# 02_stm32_power.net
KiCad netlist of a schematic drawn in Altium Designer
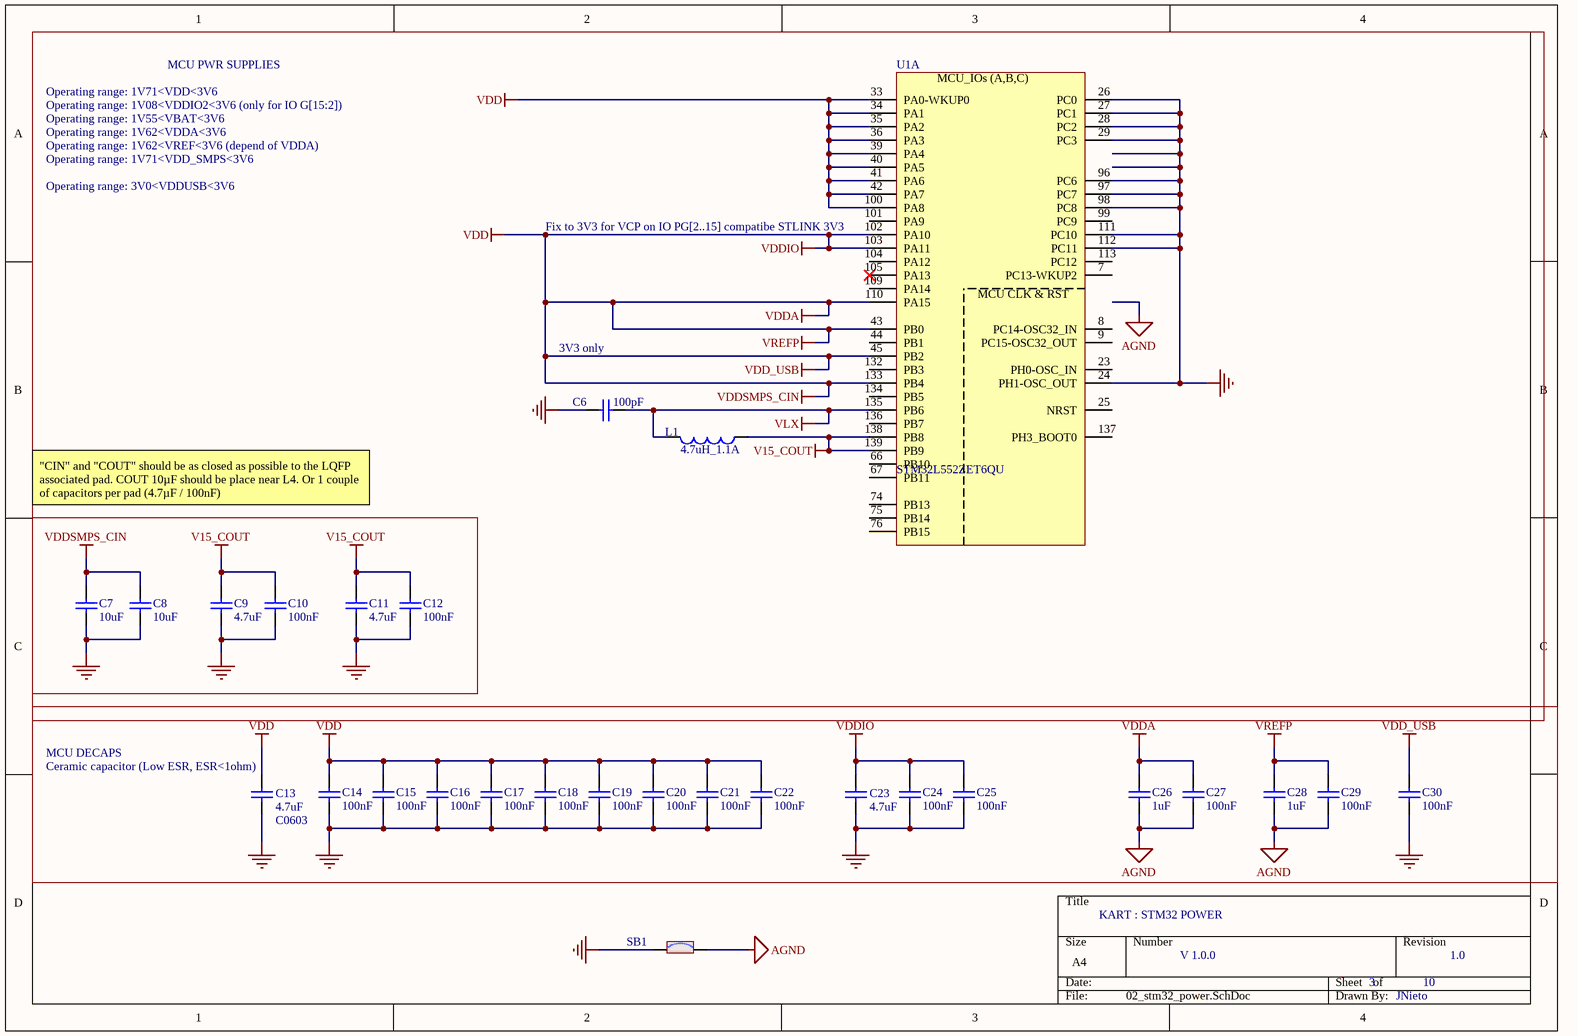
[diagram p0: 02_stm32_power.SchDoc]

(export (version "E")
  (design (tool "Eeschema 10.0.6"))
  (components
    (comp (ref "C6")
      (value "100pF")
      (footprint "C0603")
      (description "Capacitor, MLCC, 100pF, 50V, NPO, 5%, 0402, T=0,5mm")
      (fields
        (field (name "INTERNAL_PART_NUMBER") "MCD-00205")
        (field (name "MANUFACTURER_PART_NUMBER") "CC0402JRNPO9BN101")
        (field (name "PROVIDED_BY") "Subcon")
      )
      (libsource (lib "MCD_PARTS_database") (part "Capacitor"))
    )
    (comp (ref "C7")
      (value "10uF")
      (footprint "C0603")
      (description "Capacitor, MLCC, 10uF, 4V, X5R, 20%, 0402, T=0,5mm")
      (fields
        (field (name "INTERNAL_PART_NUMBER") "MCD-01355")
        (field (name "MANUFACTURER_PART_NUMBER") "GRM155R60G106ME44")
        (field (name "PROVIDED_BY") "Subcon")
      )
      (libsource (lib "MCD_PARTS_database") (part "Capacitor"))
    )
    (comp (ref "C8")
      (value "10uF")
      (footprint "C0603")
      (description "Capacitor, MLCC, 10uF, 4V, X5R, 20%, 0402, T=0,5mm")
      (fields
        (field (name "INTERNAL_PART_NUMBER") "MCD-01355")
        (field (name "MANUFACTURER_PART_NUMBER") "GRM155R60G106ME44")
        (field (name "PROVIDED_BY") "Subcon")
      )
      (libsource (lib "MCD_PARTS_database") (part "Capacitor"))
    )
    (comp (ref "C9")
      (value "4.7uF")
      (footprint "C0603")
      (description "Capacitor, MLCC, 4.7uF, 6V3, X5R, 20%, 0402, T=0,5mm")
      (fields
        (field (name "INTERNAL_PART_NUMBER") "MCD-01356")
        (field (name "MANUFACTURER_PART_NUMBER") "GRM155R60J475ME47")
        (field (name "PROVIDED_BY") "Subcon")
      )
      (libsource (lib "MCD_PARTS_database") (part "Capacitor"))
    )
    (comp (ref "C10")
      (value "100nF")
      (footprint "C0603")
      (description "Capacitor, MLCC, 100nF, 16V, X5R, 10%, 0603, T=0,8mm")
      (fields
        (field (name "INTERNAL_PART_NUMBER") "MCD-00010")
        (field (name "MANUFACTURER_PART_NUMBER") "CC0603KRX5R7BB105")
        (field (name "PROVIDED_BY") "SUBCO")
      )
      (libsource (lib "MCD_PARTS_database") (part "Capacitor"))
    )
    (comp (ref "C11")
      (value "4.7uF")
      (footprint "C0603")
      (description "Capacitor, MLCC, 4.7uF, 6V3, X5R, 20%, 0402, T=0,5mm")
      (fields
        (field (name "INTERNAL_PART_NUMBER") "MCD-01356")
        (field (name "MANUFACTURER_PART_NUMBER") "GRM155R60J475ME47")
        (field (name "PROVIDED_BY") "Subcon")
      )
      (libsource (lib "MCD_PARTS_database") (part "Capacitor"))
    )
    (comp (ref "C12")
      (value "100nF")
      (footprint "C0603")
      (description "Capacitor, MLCC, 100nF, 16V, X5R, 10%, 0603, T=0,8mm")
      (fields
        (field (name "INTERNAL_PART_NUMBER") "MCD-00010")
        (field (name "MANUFACTURER_PART_NUMBER") "CC0603KRX5R7BB105")
        (field (name "PROVIDED_BY") "SUBCO")
      )
      (libsource (lib "MCD_PARTS_database") (part "Capacitor"))
    )
    (comp (ref "C13")
      (value "4.7uF")
      (footprint "C0603")
      (description "Capacitor, MLCC, 4.7µF, 10V, X5R, 20%, 0603, T=0,8mm")
      (fields
        (field (name "INTERNAL_PART_NUMBER") "MCD-01121")
        (field (name "MANUFACTURER_PART_NUMBER") "GRM188R61A475ME15")
        (field (name "PACKAGE") "C0603")
        (field (name "PROVIDED_BY") "Subcon")
      )
      (libsource (lib "MCD_PARTS_database") (part "Capacitor"))
    )
    (comp (ref "C14")
      (value "100nF")
      (footprint "C0603")
      (description "Capacitor, MLCC, 100nF, 16V, X5R, 10%, 0603, T=0,8mm")
      (fields
        (field (name "INTERNAL_PART_NUMBER") "MCD-00010")
        (field (name "MANUFACTURER_PART_NUMBER") "CC0603KRX5R7BB105")
        (field (name "PROVIDED_BY") "SUBCO")
      )
      (libsource (lib "MCD_PARTS_database") (part "Capacitor"))
    )
    (comp (ref "C15")
      (value "100nF")
      (footprint "C0603")
      (description "Capacitor, MLCC, 100nF, 16V, X5R, 10%, 0603, T=0,8mm")
      (fields
        (field (name "INTERNAL_PART_NUMBER") "MCD-00010")
        (field (name "MANUFACTURER_PART_NUMBER") "CC0603KRX5R7BB105")
        (field (name "PROVIDED_BY") "SUBCO")
      )
      (libsource (lib "MCD_PARTS_database") (part "Capacitor"))
    )
    (comp (ref "C16")
      (value "100nF")
      (footprint "C0603")
      (description "Capacitor, MLCC, 100nF, 16V, X5R, 10%, 0603, T=0,8mm")
      (fields
        (field (name "INTERNAL_PART_NUMBER") "MCD-00010")
        (field (name "MANUFACTURER_PART_NUMBER") "CC0603KRX5R7BB105")
        (field (name "PROVIDED_BY") "SUBCO")
      )
      (libsource (lib "MCD_PARTS_database") (part "Capacitor"))
    )
    (comp (ref "C17")
      (value "100nF")
      (footprint "C0603")
      (description "Capacitor, MLCC, 100nF, 16V, X5R, 10%, 0603, T=0,8mm")
      (fields
        (field (name "INTERNAL_PART_NUMBER") "MCD-00010")
        (field (name "MANUFACTURER_PART_NUMBER") "CC0603KRX5R7BB105")
        (field (name "PROVIDED_BY") "SUBCO")
      )
      (libsource (lib "MCD_PARTS_database") (part "Capacitor"))
    )
    (comp (ref "C18")
      (value "100nF")
      (footprint "C0603")
      (description "Capacitor, MLCC, 100nF, 16V, X5R, 10%, 0603, T=0,8mm")
      (fields
        (field (name "INTERNAL_PART_NUMBER") "MCD-00010")
        (field (name "MANUFACTURER_PART_NUMBER") "CC0603KRX5R7BB105")
        (field (name "PROVIDED_BY") "SUBCO")
      )
      (libsource (lib "MCD_PARTS_database") (part "Capacitor"))
    )
    (comp (ref "C19")
      (value "100nF")
      (footprint "C0603")
      (description "Capacitor, MLCC, 100nF, 16V, X5R, 10%, 0603, T=0,8mm")
      (fields
        (field (name "INTERNAL_PART_NUMBER") "MCD-00010")
        (field (name "MANUFACTURER_PART_NUMBER") "CC0603KRX5R7BB105")
        (field (name "PROVIDED_BY") "SUBCO")
      )
      (libsource (lib "MCD_PARTS_database") (part "Capacitor"))
    )
    (comp (ref "C20")
      (value "100nF")
      (footprint "C0603")
      (description "Capacitor, MLCC, 100nF, 16V, X5R, 10%, 0603, T=0,8mm")
      (fields
        (field (name "INTERNAL_PART_NUMBER") "MCD-00010")
        (field (name "MANUFACTURER_PART_NUMBER") "CC0603KRX5R7BB105")
        (field (name "PROVIDED_BY") "SUBCO")
      )
      (libsource (lib "MCD_PARTS_database") (part "Capacitor"))
    )
    (comp (ref "C21")
      (value "100nF")
      (footprint "C0603")
      (description "Capacitor, MLCC, 100nF, 16V, X5R, 10%, 0603, T=0,8mm")
      (fields
        (field (name "INTERNAL_PART_NUMBER") "MCD-00010")
        (field (name "MANUFACTURER_PART_NUMBER") "CC0603KRX5R7BB105")
        (field (name "PROVIDED_BY") "SUBCO")
      )
      (libsource (lib "MCD_PARTS_database") (part "Capacitor"))
    )
    (comp (ref "C22")
      (value "100nF")
      (footprint "C0603")
      (description "Capacitor, MLCC, 100nF, 16V, X5R, 10%, 0603, T=0,8mm")
      (fields
        (field (name "INTERNAL_PART_NUMBER") "MCD-00010")
        (field (name "MANUFACTURER_PART_NUMBER") "CC0603KRX5R7BB105")
        (field (name "PROVIDED_BY") "SUBCO")
      )
      (libsource (lib "MCD_PARTS_database") (part "Capacitor"))
    )
    (comp (ref "C23")
      (value "4.7uF")
      (footprint "C0603")
      (description "Capacitor, MLCC, 4.7µF, 10V, X5R, 20%, 0603, T=0,8mm")
      (fields
        (field (name "INTERNAL_PART_NUMBER") "MCD-01121")
        (field (name "MANUFACTURER_PART_NUMBER") "GRM188R61A475ME15")
        (field (name "PROVIDED_BY") "Subcon")
      )
      (libsource (lib "MCD_PARTS_database") (part "Capacitor"))
    )
    (comp (ref "C24")
      (value "100nF")
      (footprint "C0603")
      (description "Capacitor, MLCC, 100nF, 16V, X5R, 10%, 0603, T=0,8mm")
      (fields
        (field (name "INTERNAL_PART_NUMBER") "MCD-00010")
        (field (name "MANUFACTURER_PART_NUMBER") "CC0603KRX5R7BB105")
        (field (name "PROVIDED_BY") "SUBCO")
      )
      (libsource (lib "MCD_PARTS_database") (part "Capacitor"))
    )
    (comp (ref "C25")
      (value "100nF")
      (footprint "C0603")
      (description "Capacitor, MLCC, 100nF, 16V, X5R, 10%, 0603, T=0,8mm")
      (fields
        (field (name "INTERNAL_PART_NUMBER") "MCD-00010")
        (field (name "MANUFACTURER_PART_NUMBER") "CC0603KRX5R7BB105")
        (field (name "PROVIDED_BY") "SUBCO")
      )
      (libsource (lib "MCD_PARTS_database") (part "Capacitor"))
    )
    (comp (ref "C26")
      (value "1uF")
      (footprint "C0603")
      (description "Capacitor, MLCC, 1uF, 16V, X5R, 10%, 0603, T=0,8mm")
      (fields
        (field (name "INTERNAL_PART_NUMBER") "MCD-00010")
        (field (name "MANUFACTURER_PART_NUMBER") "CC0603KRX5R7BB105")
        (field (name "PROVIDED_BY") "SUBCO")
      )
      (libsource (lib "MCD_PARTS_database") (part "Capacitor"))
    )
    (comp (ref "C27")
      (value "100nF")
      (footprint "C0603")
      (description "Capacitor, MLCC, 100nF, 16V, X5R, 10%, 0603, T=0,8mm")
      (fields
        (field (name "INTERNAL_PART_NUMBER") "MCD-00010")
        (field (name "MANUFACTURER_PART_NUMBER") "CC0603KRX5R7BB105")
        (field (name "PROVIDED_BY") "SUBCO")
      )
      (libsource (lib "MCD_PARTS_database") (part "Capacitor"))
    )
    (comp (ref "C28")
      (value "1uF")
      (footprint "C0603")
      (description "Capacitor, MLCC, 1uF, 16V, X5R, 10%, 0603, T=0,8mm")
      (fields
        (field (name "INTERNAL_PART_NUMBER") "MCD-00010")
        (field (name "MANUFACTURER_PART_NUMBER") "CC0603KRX5R7BB105")
        (field (name "PROVIDED_BY") "SUBCO")
      )
      (libsource (lib "MCD_PARTS_database") (part "Capacitor"))
    )
    (comp (ref "C29")
      (value "100nF")
      (footprint "C0603")
      (description "Capacitor, MLCC, 100nF, 16V, X5R, 10%, 0603, T=0,8mm")
      (fields
        (field (name "INTERNAL_PART_NUMBER") "MCD-00010")
        (field (name "MANUFACTURER_PART_NUMBER") "CC0603KRX5R7BB105")
        (field (name "PROVIDED_BY") "SUBCO")
      )
      (libsource (lib "MCD_PARTS_database") (part "Capacitor"))
    )
    (comp (ref "C30")
      (value "100nF")
      (footprint "C0603")
      (description "Capacitor, MLCC, 100nF, 16V, X5R, 10%, 0603, T=0,8mm")
      (fields
        (field (name "INTERNAL_PART_NUMBER") "MCD-00010")
        (field (name "MANUFACTURER_PART_NUMBER") "CC0603KRX5R7BB105")
        (field (name "PROVIDED_BY") "SUBCO")
      )
      (libsource (lib "MCD_PARTS_database") (part "Capacitor"))
    )
    (comp (ref "L1")
      (value "4.7uH_1.1A")
      (footprint "IND_TDK_MLP2016H4R7MT0S1")
      (description "Power Inductor 4.7uH 1.1A 160 mOHM 20% SMD Multilayer ferrite.")
      (fields
        (field (name "INTERNAL_PART_NUMBER") "MCD-01786")
        (field (name "MANUFACTURER_PART_NUMBER") "MLP2016H4R7MT0S1")
        (field (name "PROVIDED_BY") "SUBCO")
      )
      (libsource (lib "MCD_PARTS_database") (part "Inductor"))
    )
    (comp (ref "SB1")
      (value "~")
      (footprint "SOLDER-BRIDGE_R0603-0R")
      (description "Solder Bridge ON")
      (fields (field (name "INTERNAL_PART_NUMBER") "MCD-00071") (field (name "PROVIDED_BY") "Subcon"))
      (libsource (lib "MCD_PARTS_database") (part "SB_ON"))
    )
    (comp (ref "U1")
      (value "STM32L552ZET6QU")
      (footprint "ICC_LQFP144_20X20_P050")
      (description "STM32L552ZET6Q MCU,LQFP144 20x20, 0.5, no AES, Q for Int SMPS")
      (fields
        (field (name "INTERNAL_PART_NUMBER") "MCD-01055")
        (field (name "MANUFACTURER") "STMICROELECTRONICS")
        (field (name "PROVIDED_BY") "SUBCO with ST control")
      )
      (libsource (lib "MCD_PARTS_database") (part "STM32L552ZET6QU"))
    )
  )
  (nets
    (net (code "1") (name "AGND") (class "Default")
      (node (ref "C26") (pin "2") (pinfunction "2_2") (pintype "passive"))
      (node (ref "C27") (pin "1") (pinfunction "1_1") (pintype "passive"))
      (node (ref "C28") (pin "2") (pinfunction "2_2") (pintype "passive"))
      (node (ref "C29") (pin "1") (pinfunction "1_1") (pintype "passive"))
      (node (ref "SB1") (pin "2") (pinfunction "2_2") (pintype "passive"))
    )
    (net (code "2") (name "GND") (class "Default")
      (node (ref "C10") (pin "1") (pinfunction "1_1") (pintype "passive"))
      (node (ref "C11") (pin "1") (pinfunction "1_1") (pintype "passive"))
      (node (ref "C12") (pin "1") (pinfunction "1_1") (pintype "passive"))
      (node (ref "C13") (pin "1") (pinfunction "1_1") (pintype "passive"))
      (node (ref "C14") (pin "1") (pinfunction "1_1") (pintype "passive"))
      (node (ref "C15") (pin "1") (pinfunction "1_1") (pintype "passive"))
      (node (ref "C16") (pin "1") (pinfunction "1_1") (pintype "passive"))
      (node (ref "C17") (pin "1") (pinfunction "1_1") (pintype "passive"))
      (node (ref "C18") (pin "1") (pinfunction "1_1") (pintype "passive"))
      (node (ref "C19") (pin "1") (pinfunction "1_1") (pintype "passive"))
      (node (ref "C20") (pin "1") (pinfunction "1_1") (pintype "passive"))
      (node (ref "C21") (pin "1") (pinfunction "1_1") (pintype "passive"))
      (node (ref "C22") (pin "1") (pinfunction "1_1") (pintype "passive"))
      (node (ref "C23") (pin "1") (pinfunction "1_1") (pintype "passive"))
      (node (ref "C24") (pin "1") (pinfunction "1_1") (pintype "passive"))
      (node (ref "C25") (pin "1") (pinfunction "1_1") (pintype "passive"))
      (node (ref "C30") (pin "1") (pinfunction "1_1") (pintype "passive"))
      (node (ref "C6") (pin "1") (pinfunction "1_1") (pintype "passive"))
      (node (ref "C7") (pin "1") (pinfunction "1_1") (pintype "passive"))
      (node (ref "C8") (pin "1") (pinfunction "1_1") (pintype "passive"))
      (node (ref "C9") (pin "1") (pinfunction "1_1") (pintype "passive"))
      (node (ref "SB1") (pin "1") (pinfunction "1_1") (pintype "passive"))
      (node (ref "U1") (pin "111") (pinfunction "PC10_111") (pintype "passive"))
      (node (ref "U1") (pin "112") (pinfunction "PC11_112") (pintype "passive"))
      (node (ref "U1") (pin "24") (pinfunction "PH1-OSC_OUT_24") (pintype "passive"))
      (node (ref "U1") (pin "26") (pinfunction "PC0_26") (pintype "passive"))
      (node (ref "U1") (pin "27") (pinfunction "PC1_27") (pintype "passive"))
      (node (ref "U1") (pin "28") (pinfunction "PC2_28") (pintype "passive"))
      (node (ref "U1") (pin "29") (pinfunction "PC3_29") (pintype "passive"))
      (node (ref "U1") (pin "96") (pinfunction "PC6_96") (pintype "passive"))
      (node (ref "U1") (pin "97") (pinfunction "PC7_97") (pintype "passive"))
      (node (ref "U1") (pin "98") (pinfunction "PC8_98") (pintype "passive"))
    )
    (net (code "3") (name "V15_COUT") (class "Default")
      (node (ref "C10") (pin "2") (pinfunction "2_2") (pintype "passive"))
      (node (ref "C11") (pin "2") (pinfunction "2_2") (pintype "passive"))
      (node (ref "C12") (pin "2") (pinfunction "2_2") (pintype "passive"))
      (node (ref "C9") (pin "2") (pinfunction "2_2") (pintype "passive"))
      (node (ref "L1") (pin "1") (pinfunction "1_1") (pintype "passive"))
      (node (ref "U1") (pin "138") (pinfunction "PB8_138") (pintype "passive"))
      (node (ref "U1") (pin "139") (pinfunction "PB9_139") (pintype "passive"))
    )
    (net (code "4") (name "VDD") (class "Default")
      (node (ref "C13") (pin "2") (pinfunction "2_2") (pintype "passive"))
      (node (ref "C14") (pin "2") (pinfunction "2_2") (pintype "passive"))
      (node (ref "C15") (pin "2") (pinfunction "2_2") (pintype "passive"))
      (node (ref "C16") (pin "2") (pinfunction "2_2") (pintype "passive"))
      (node (ref "C17") (pin "2") (pinfunction "2_2") (pintype "passive"))
      (node (ref "C18") (pin "2") (pinfunction "2_2") (pintype "passive"))
      (node (ref "C19") (pin "2") (pinfunction "2_2") (pintype "passive"))
      (node (ref "C20") (pin "2") (pinfunction "2_2") (pintype "passive"))
      (node (ref "C21") (pin "2") (pinfunction "2_2") (pintype "passive"))
      (node (ref "C22") (pin "2") (pinfunction "2_2") (pintype "passive"))
      (node (ref "C23") (pin "2") (pinfunction "2_2") (pintype "passive"))
      (node (ref "C24") (pin "2") (pinfunction "2_2") (pintype "passive"))
      (node (ref "C25") (pin "2") (pinfunction "2_2") (pintype "passive"))
      (node (ref "C26") (pin "1") (pinfunction "1_1") (pintype "passive"))
      (node (ref "C27") (pin "2") (pinfunction "2_2") (pintype "passive"))
      (node (ref "C28") (pin "1") (pinfunction "1_1") (pintype "passive"))
      (node (ref "C29") (pin "2") (pinfunction "2_2") (pintype "passive"))
      (node (ref "C30") (pin "2") (pinfunction "2_2") (pintype "passive"))
      (node (ref "C7") (pin "2") (pinfunction "2_2") (pintype "passive"))
      (node (ref "C8") (pin "2") (pinfunction "2_2") (pintype "passive"))
      (node (ref "U1") (pin "100") (pinfunction "PA8_100") (pintype "passive"))
      (node (ref "U1") (pin "102") (pinfunction "PA10_102") (pintype "passive"))
      (node (ref "U1") (pin "103") (pinfunction "PA11_103") (pintype "passive"))
      (node (ref "U1") (pin "110") (pinfunction "PA15_110") (pintype "passive"))
      (node (ref "U1") (pin "133") (pinfunction "PB4_133") (pintype "passive"))
      (node (ref "U1") (pin "33") (pinfunction "PA0-WKUP0_33") (pintype "passive"))
      (node (ref "U1") (pin "34") (pinfunction "PA1_34") (pintype "passive"))
      (node (ref "U1") (pin "35") (pinfunction "PA2_35") (pintype "passive"))
      (node (ref "U1") (pin "36") (pinfunction "PA3_36") (pintype "passive"))
      (node (ref "U1") (pin "39") (pinfunction "PA4_39") (pintype "passive"))
      (node (ref "U1") (pin "40") (pinfunction "PA5_40") (pintype "passive"))
      (node (ref "U1") (pin "41") (pinfunction "PA6_41") (pintype "passive"))
      (node (ref "U1") (pin "42") (pinfunction "PA7_42") (pintype "passive"))
      (node (ref "U1") (pin "43") (pinfunction "PB0_43") (pintype "passive"))
      (node (ref "U1") (pin "45") (pinfunction "PB2_45") (pintype "passive"))
    )
    (net (code "5") (name "VLX") (class "Default")
      (node (ref "C6") (pin "2") (pinfunction "2_2") (pintype "passive"))
      (node (ref "L1") (pin "2") (pinfunction "2_2") (pintype "passive"))
      (node (ref "U1") (pin "135") (pinfunction "PB6_135") (pintype "passive"))
    )
    (net (code "6") (name "unconnected-(U1A-NRST-Pad25)") (class "Default")
      (node (ref "U1") (pin "25") (pinfunction "NRST_25") (pintype "passive"))
    )
    (net (code "7") (name "unconnected-(U1A-PA9-Pad101)") (class "Default")
      (node (ref "U1") (pin "101") (pinfunction "PA9_101") (pintype "passive"))
    )
    (net (code "8") (name "unconnected-(U1A-PA12-Pad104)") (class "Default")
      (node (ref "U1") (pin "104") (pinfunction "PA12_104") (pintype "passive"))
    )
    (net (code "9") (name "unconnected-(U1A-PA13-Pad105)") (class "Default")
      (node (ref "U1") (pin "105") (pinfunction "PA13_105") (pintype "passive+no_connect"))
    )
    (net (code "10") (name "unconnected-(U1A-PA14-Pad109)") (class "Default")
      (node (ref "U1") (pin "109") (pinfunction "PA14_109") (pintype "passive"))
    )
    (net (code "11") (name "unconnected-(U1A-PB1-Pad44)") (class "Default")
      (node (ref "U1") (pin "44") (pinfunction "PB1_44") (pintype "passive"))
    )
    (net (code "12") (name "unconnected-(U1A-PB3-Pad132)") (class "Default")
      (node (ref "U1") (pin "132") (pinfunction "PB3_132") (pintype "passive"))
    )
    (net (code "13") (name "unconnected-(U1A-PB5-Pad134)") (class "Default")
      (node (ref "U1") (pin "134") (pinfunction "PB5_134") (pintype "passive"))
    )
    (net (code "14") (name "unconnected-(U1A-PB7-Pad136)") (class "Default")
      (node (ref "U1") (pin "136") (pinfunction "PB7_136") (pintype "passive"))
    )
    (net (code "15") (name "unconnected-(U1A-PB10-Pad66)") (class "Default")
      (node (ref "U1") (pin "66") (pinfunction "PB10_66") (pintype "passive"))
    )
    (net (code "16") (name "unconnected-(U1A-PB11-Pad67)") (class "Default")
      (node (ref "U1") (pin "67") (pinfunction "PB11_67") (pintype "passive"))
    )
    (net (code "17") (name "unconnected-(U1A-PB13-Pad74)") (class "Default")
      (node (ref "U1") (pin "74") (pinfunction "PB13_74") (pintype "passive"))
    )
    (net (code "18") (name "unconnected-(U1A-PB14-Pad75)") (class "Default")
      (node (ref "U1") (pin "75") (pinfunction "PB14_75") (pintype "passive"))
    )
    (net (code "19") (name "unconnected-(U1A-PB15-Pad76)") (class "Default")
      (node (ref "U1") (pin "76") (pinfunction "PB15_76") (pintype "passive"))
    )
    (net (code "20") (name "unconnected-(U1A-PC9-Pad99)") (class "Default")
      (node (ref "U1") (pin "99") (pinfunction "PC9_99") (pintype "passive"))
    )
    (net (code "21") (name "unconnected-(U1A-PC12-Pad113)") (class "Default")
      (node (ref "U1") (pin "113") (pinfunction "PC12_113") (pintype "passive"))
    )
    (net (code "22") (name "unconnected-(U1A-PC13-WKUP2-Pad7)") (class "Default")
      (node (ref "U1") (pin "7") (pinfunction "PC13-WKUP2_7") (pintype "passive"))
    )
    (net (code "23") (name "unconnected-(U1A-PC14-OSC32_IN-Pad8)") (class "Default")
      (node (ref "U1") (pin "8") (pinfunction "PC14-OSC32_IN_8") (pintype "passive"))
    )
    (net (code "24") (name "unconnected-(U1A-PC15-OSC32_OUT-Pad9)") (class "Default")
      (node (ref "U1") (pin "9") (pinfunction "PC15-OSC32_OUT_9") (pintype "passive"))
    )
    (net (code "25") (name "unconnected-(U1A-PH0-OSC_IN-Pad23)") (class "Default")
      (node (ref "U1") (pin "23") (pinfunction "PH0-OSC_IN_23") (pintype "passive"))
    )
    (net (code "26") (name "unconnected-(U1A-PH3_BOOT0-Pad137)") (class "Default")
      (node (ref "U1") (pin "137") (pinfunction "PH3_BOOT0_137") (pintype "passive"))
    )
  )
)
